# Grove_-_Barometer_Sensor_v1_0b.net
KiCad netlist of a schematic drawn in EAGLE
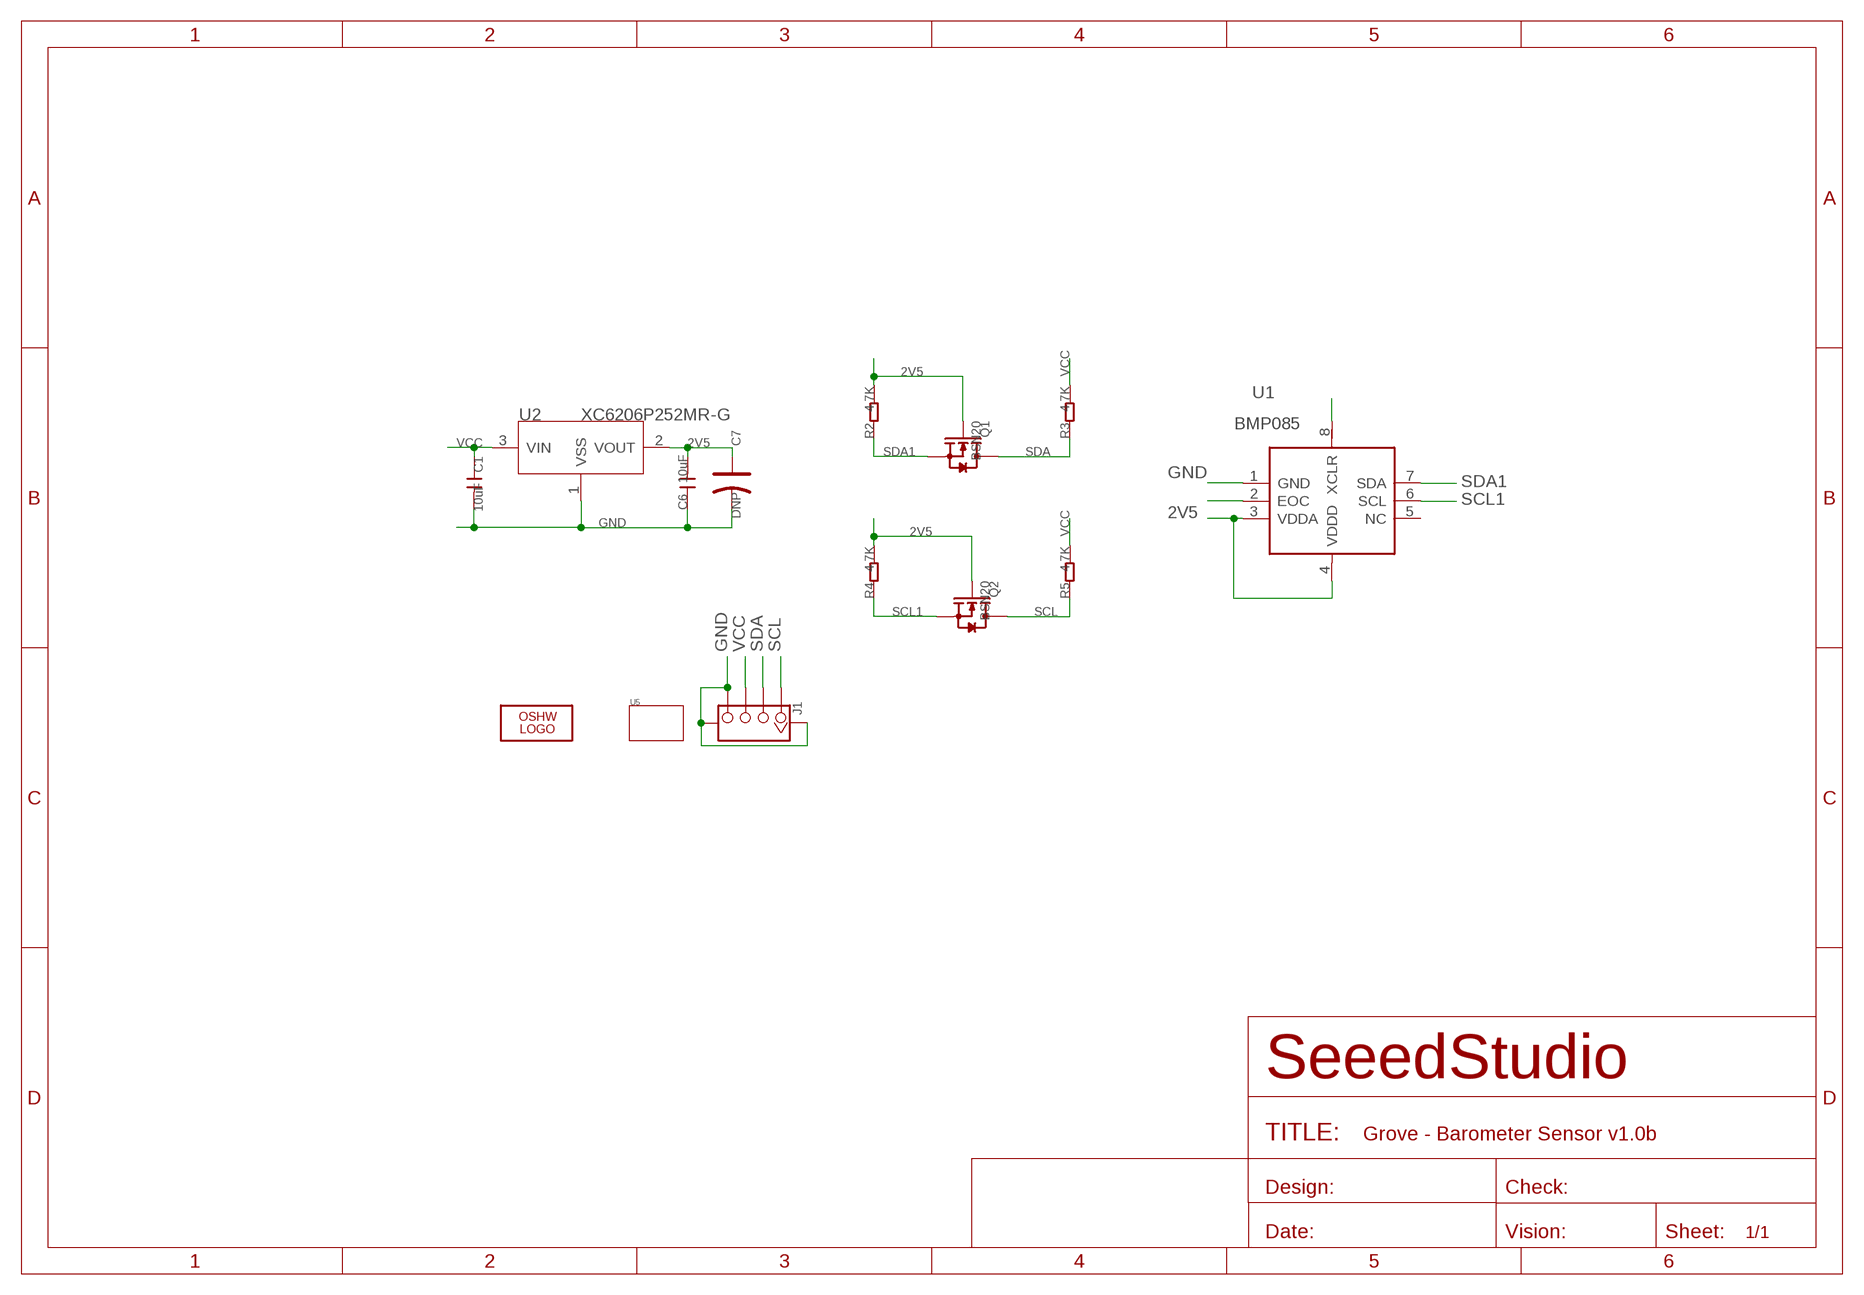
[diagram p0: schematic, sheet 1]

(export (version "E")
  (design (tool "Eeschema 10.0.6"))
  (components
    (comp (ref "C1")
      (value "10uF")
      (footprint "eagle-import:C0805")
      (libsource (lib "eagle-import") (part "C-0805"))
    )
    (comp (ref "C6")
      (value "10uF")
      (footprint "eagle-import:C0805")
      (libsource (lib "eagle-import") (part "C-0805"))
    )
    (comp (ref "C7")
      (value "DNP")
      (footprint "eagle-import:AVX-A")
      (libsource (lib "eagle-import") (part "CAP-AVX-A"))
    )
    (comp (ref "J1")
      (value "TWIG-4P-2.0-SMD-FEMALE-REINFORCE'DD'")
      (footprint "eagle-import:4P-SMD-2.0")
      (libsource (lib "eagle-import") (part "TWIG-4P-2.0-SMD-FEMALE-REINFORCE'DD'"))
    )
    (comp (ref "LOGO2")
      (value "LOGO-OSHW-FILLX0200-NT")
      (footprint "eagle-import:OSHW_FILLX200_NOTEXT")
      (libsource (lib "eagle-import") (part "LOGO-OSHW-FILLX0200-NT"))
    )
    (comp (ref "Q1")
      (value "BSN20")
      (footprint "eagle-import:SOT23")
      (libsource (lib "eagle-import") (part "MOSFET-N'SOT23'"))
    )
    (comp (ref "Q2")
      (value "BSN20")
      (footprint "eagle-import:SOT23")
      (libsource (lib "eagle-import") (part "MOSFET-N'SOT23'"))
    )
    (comp (ref "R2")
      (value "4.7K")
      (footprint "eagle-import:R0603")
      (libsource (lib "eagle-import") (part "R-0603"))
    )
    (comp (ref "R3")
      (value "4.7K")
      (footprint "eagle-import:R0603")
      (libsource (lib "eagle-import") (part "R-0603"))
    )
    (comp (ref "R4")
      (value "4.7K")
      (footprint "eagle-import:R0603")
      (libsource (lib "eagle-import") (part "R-0603"))
    )
    (comp (ref "R5")
      (value "4.7K")
      (footprint "eagle-import:R0603")
      (libsource (lib "eagle-import") (part "R-0603"))
    )
    (comp (ref "U1")
      (value "BMP085")
      (footprint "eagle-import:LCC8")
      (libsource (lib "eagle-import") (part "BMP085"))
    )
    (comp (ref "U2")
      (value "XC6206P252MR-G")
      (footprint "eagle-import:SOT23")
      (libsource (lib "eagle-import") (part "XC6206MR"))
    )
    (comp (ref "U5")
      (value "TWIG-1U")
      (footprint "eagle-import:1U-DIM-W_-DRILL")
      (libsource (lib "eagle-import") (part "TWIG-1U"))
    )
  )
  (nets
    (net (code "1") (name "/2V5") (class "Default")
      (node (ref "C6") (pin "2") (pinfunction "2_2") (pintype "passive"))
      (node (ref "C7") (pin "+") (pinfunction "+_+") (pintype "passive"))
      (node (ref "Q1") (pin "1") (pinfunction "G_1") (pintype "passive"))
      (node (ref "Q2") (pin "1") (pinfunction "G_1") (pintype "passive"))
      (node (ref "R2") (pin "2") (pinfunction "2_2") (pintype "passive"))
      (node (ref "R4") (pin "2") (pinfunction "2_2") (pintype "passive"))
      (node (ref "U1") (pin "3") (pinfunction "VDDA_3") (pintype "power_in"))
      (node (ref "U1") (pin "4") (pinfunction "VDDD_4") (pintype "power_in"))
      (node (ref "U2") (pin "2") (pinfunction "VOUT_2") (pintype "output"))
    )
    (net (code "2") (name "/GND") (class "Default")
      (node (ref "C1") (pin "2") (pinfunction "2_2") (pintype "passive"))
      (node (ref "C6") (pin "1") (pinfunction "1_1") (pintype "passive"))
      (node (ref "C7") (pin "-") (pinfunction "-_-") (pintype "passive"))
      (node (ref "J1") (pin "4") (pinfunction "4_4") (pintype "bidirectional"))
      (node (ref "J1") (pin "SS1") (pinfunction "SS1_SS1") (pintype "bidirectional"))
      (node (ref "J1") (pin "SS2") (pinfunction "SS2_SS2") (pintype "bidirectional"))
      (node (ref "U1") (pin "1") (pinfunction "GND_1") (pintype "power_in"))
      (node (ref "U2") (pin "1") (pinfunction "VSS_1") (pintype "power_in"))
    )
    (net (code "3") (name "/SCL") (class "Default")
      (node (ref "J1") (pin "1") (pinfunction "1_1") (pintype "bidirectional"))
      (node (ref "Q2") (pin "3") (pinfunction "D_3") (pintype "passive"))
      (node (ref "R5") (pin "1") (pinfunction "1_1") (pintype "passive"))
    )
    (net (code "4") (name "/SCL1") (class "Default")
      (node (ref "Q2") (pin "2") (pinfunction "S_2") (pintype "passive"))
      (node (ref "R4") (pin "1") (pinfunction "1_1") (pintype "passive"))
      (node (ref "U1") (pin "6") (pinfunction "SCL_6") (pintype "input"))
    )
    (net (code "5") (name "/SDA") (class "Default")
      (node (ref "J1") (pin "2") (pinfunction "2_2") (pintype "bidirectional"))
      (node (ref "Q1") (pin "3") (pinfunction "D_3") (pintype "passive"))
      (node (ref "R3") (pin "1") (pinfunction "1_1") (pintype "passive"))
    )
    (net (code "6") (name "/SDA1") (class "Default")
      (node (ref "Q1") (pin "2") (pinfunction "S_2") (pintype "passive"))
      (node (ref "R2") (pin "1") (pinfunction "1_1") (pintype "passive"))
      (node (ref "U1") (pin "7") (pinfunction "SDA_7") (pintype "bidirectional"))
    )
    (net (code "7") (name "/VCC") (class "Default")
      (node (ref "C1") (pin "1") (pinfunction "1_1") (pintype "passive"))
      (node (ref "J1") (pin "3") (pinfunction "3_3") (pintype "bidirectional"))
      (node (ref "R3") (pin "2") (pinfunction "2_2") (pintype "passive"))
      (node (ref "R5") (pin "2") (pinfunction "2_2") (pintype "passive"))
      (node (ref "U2") (pin "3") (pinfunction "VIN_3") (pintype "input"))
    )
    (net (code "8") (name "unconnected-(U1-EOC-Pad2)") (class "Default")
      (node (ref "U1") (pin "2") (pinfunction "EOC_2") (pintype "output"))
    )
    (net (code "9") (name "unconnected-(U1-NC-Pad5)") (class "Default")
      (node (ref "U1") (pin "5") (pinfunction "NC_5") (pintype "no_connect"))
    )
    (net (code "10") (name "unconnected-(U1-XCLR-Pad8)") (class "Default")
      (node (ref "U1") (pin "8") (pinfunction "XCLR_8") (pintype "input"))
    )
  )
)
